# Sheet1.net
KiCad netlist of a schematic drawn in Altium Designer
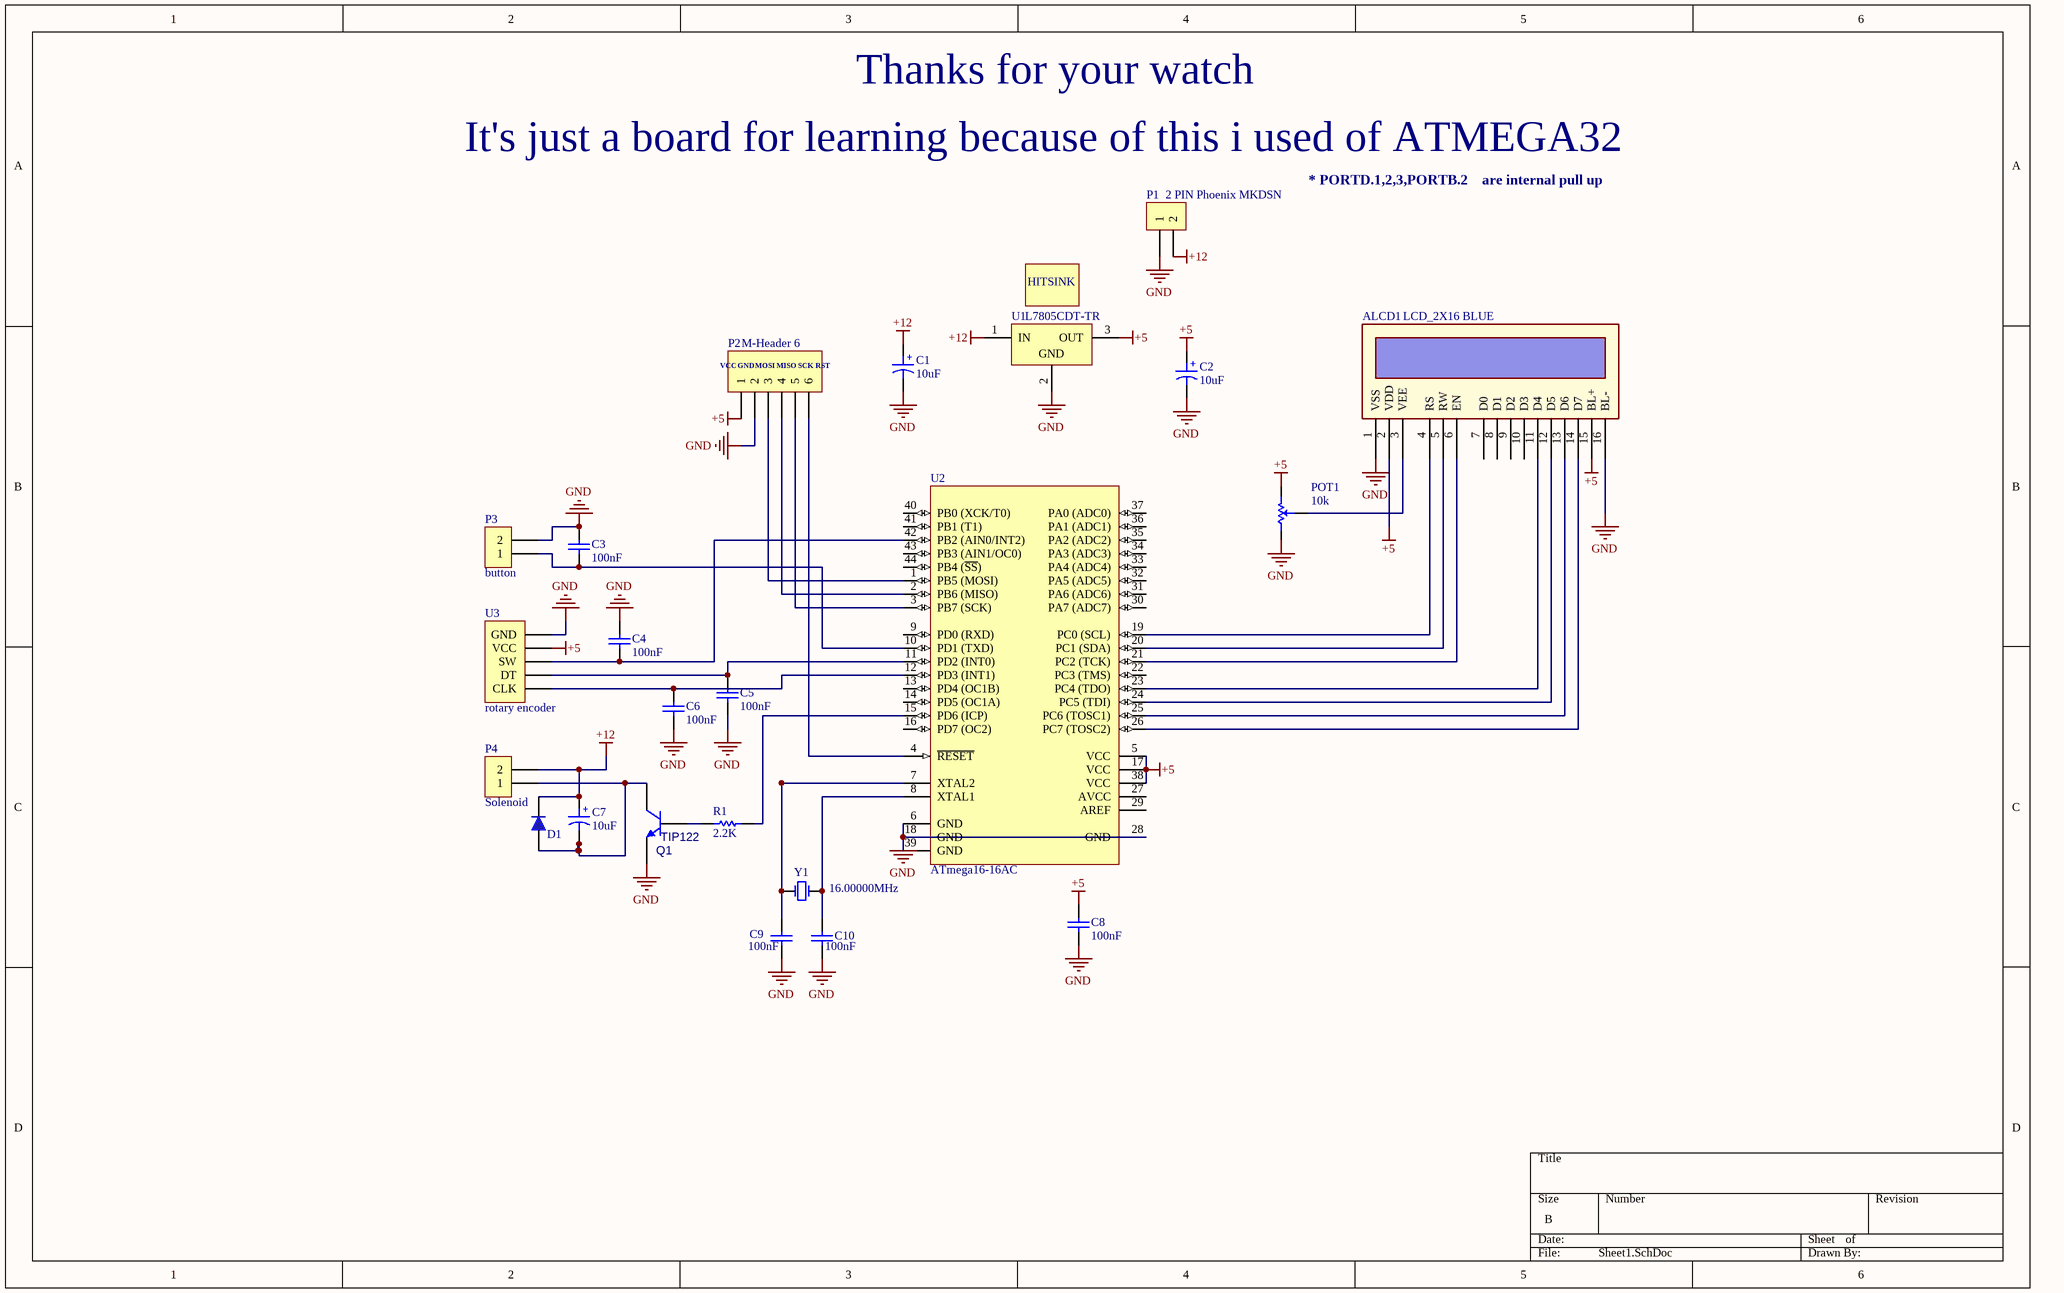
[diagram p0: Sheet1.SchDoc]

(export (version "E")
  (design (tool "Eeschema 10.0.6"))
  (components
    (comp (ref "1")
      (value "Hitsink")
      (footprint "HITSINK 1")
      (libsource (lib "Optoelectronics") (part "Hitsink"))
    )
    (comp (ref "ALCD1")
      (value "LCD_2X16 BLUE")
      (footprint "LCD_2X16 BLUE")
      (libsource (lib "Optoelectronics") (part "LCD_2X16 BLUE"))
    )
    (comp (ref "C1")
      (value "10uF")
      (footprint "Cap 6.3x12-2.5")
      (description "Capacitor DIP")
      (libsource (lib "Inactive components") (part "Capacitor DIP"))
    )
    (comp (ref "C2")
      (value "10uF")
      (footprint "Cap 6.3x12-2.5")
      (description "Capacitor DIP")
      (libsource (lib "Inactive components") (part "Capacitor DIP"))
    )
    (comp (ref "C3")
      (value "100nF")
      (footprint "CAP1206")
      (description "Capacitor SMD")
      (libsource (lib "Inactive components") (part "Capacitor SMD"))
    )
    (comp (ref "C4")
      (value "100nF")
      (footprint "CAP1206")
      (description "Capacitor SMD")
      (libsource (lib "Inactive components") (part "Capacitor SMD"))
    )
    (comp (ref "C5")
      (value "100nF")
      (footprint "CAP1206")
      (description "Capacitor SMD")
      (libsource (lib "Inactive components") (part "Capacitor SMD"))
    )
    (comp (ref "C6")
      (value "100nF")
      (footprint "CAP1206")
      (description "Capacitor SMD")
      (libsource (lib "Inactive components") (part "Capacitor SMD"))
    )
    (comp (ref "C7")
      (value "10uF")
      (footprint "Cap 5x12-2")
      (description "Capacitor DIP")
      (libsource (lib "Inactive components") (part "Capacitor DIP"))
    )
    (comp (ref "C8")
      (value "100nF")
      (footprint "CAP1206")
      (description "Capacitor SMD")
      (libsource (lib "Inactive components") (part "Capacitor SMD"))
    )
    (comp (ref "C9")
      (value "100nF")
      (footprint "CAP1206")
      (description "Capacitor SMD")
      (libsource (lib "Inactive components") (part "Capacitor SMD"))
    )
    (comp (ref "C10")
      (value "100nF")
      (footprint "CAP1206")
      (description "Capacitor SMD")
      (libsource (lib "Inactive components") (part "Capacitor SMD"))
    )
    (comp (ref "D1")
      (value "1n4007")
      (footprint "Diode 1N4007 SMD")
      (description "Diode 1n4007")
      (libsource (lib "Semiconductors") (part "Diode 1n4007"))
    )
    (comp (ref "P1")
      (value "2 PIN Phoenix MKDSN")
      (footprint "2 PIN Phoenix MKDSN")
      (libsource (lib "") (part "2 PIN Phoenix MKDSN_1"))
    )
    (comp (ref "P2")
      (value "M-Header 6")
      (footprint "M-Header 6")
      (libsource (lib "Connectors") (part "M-Header 6"))
    )
    (comp (ref "P3")
      (value "button")
      (footprint "2 PIN Phoenix MKDSN")
      (libsource (lib "Connectors") (part "2 PIN Phoenix MKDSN"))
    )
    (comp (ref "P4")
      (value "Solenoid")
      (footprint "2 PIN Phoenix MKDSN")
      (libsource (lib "Connectors") (part "2 PIN Phoenix MKDSN"))
    )
    (comp (ref "POT1")
      (value "10k")
      (footprint "POT MULTITURN")
      (libsource (lib "Inactive components") (part "Potentiometer"))
    )
    (comp (ref "Q1") (value "TIP122") (footprint "TIP122") (libsource (lib "Semiconductors") (part "TIP122")))
    (comp (ref "R1")
      (value "2.2K")
      (footprint "RES1206")
      (description "Resistor SMD")
      (libsource (lib "Inactive components") (part "Resistor SMD"))
    )
    (comp (ref "U1")
      (value "L7805CDT-TR")
      (footprint "TO-263")
      (libsource (lib "Semiconductors") (part "L7805CDT-TR"))
    )
    (comp (ref "U2")
      (value "ATmega16-16AC")
      (footprint "44A")
      (description "8-Bit AVR Microcontroller with 16K Bytes of In-System Programmable Flash Memory")
      (fields (field (name "PUBLISHER") "Altium Limited"))
      (libsource (lib "Atmel Microcontroller 8-Bit AVR") (part "ATmega16-16AC"))
    )
    (comp (ref "U3")
      (value "rotary encoder")
      (footprint "rotary encoder")
      (libsource (lib "Modules") (part "rotary encoder"))
    )
    (comp (ref "Y1")
      (value "16.00000MHz")
      (footprint "CRYSTAL Small")
      (description "XTAL DIP")
      (libsource (lib "Inactive components") (part "XTAL DIP"))
    )
  )
  (nets
    (net (code "1") (name "+5") (class "Default")
      (node (ref "ALCD1") (pin "15") (pinfunction "BL+_15") (pintype "passive"))
      (node (ref "ALCD1") (pin "2") (pinfunction "VDD_2") (pintype "passive"))
      (node (ref "C2") (pin "1") (pinfunction "1_1") (pintype "passive"))
      (node (ref "C8") (pin "2") (pinfunction "2_2") (pintype "passive"))
      (node (ref "P2") (pin "1") (pinfunction "1_1") (pintype "passive"))
      (node (ref "POT1") (pin "2") (pinfunction "CW_2") (pintype "passive"))
      (node (ref "U1") (pin "3") (pinfunction "OUT_3") (pintype "power_in"))
      (node (ref "U2") (pin "17") (pinfunction "VCC_17") (pintype "power_in"))
      (node (ref "U2") (pin "38") (pinfunction "VCC_38") (pintype "power_in"))
      (node (ref "U2") (pin "5") (pinfunction "VCC_5") (pintype "power_in"))
      (node (ref "U3") (pin "4") (pinfunction "VCC_4") (pintype "passive"))
    )
    (net (code "2") (name "+12") (class "Default")
      (node (ref "C1") (pin "1") (pinfunction "1_1") (pintype "passive"))
      (node (ref "C7") (pin "1") (pinfunction "1_1") (pintype "passive"))
      (node (ref "D1") (pin "2") (pintype "passive"))
      (node (ref "P1") (pin "2") (pinfunction "2_2") (pintype "passive"))
      (node (ref "P4") (pin "2") (pinfunction "2_2") (pintype "passive"))
      (node (ref "U1") (pin "1") (pinfunction "IN_1") (pintype "power_in"))
    )
    (net (code "3") (name "GND") (class "Default")
      (node (ref "ALCD1") (pin "1") (pinfunction "VSS_1") (pintype "passive"))
      (node (ref "ALCD1") (pin "16") (pinfunction "BL-_16") (pintype "passive"))
      (node (ref "C1") (pin "2") (pinfunction "2_2") (pintype "passive"))
      (node (ref "C10") (pin "1") (pinfunction "1_1") (pintype "passive"))
      (node (ref "C2") (pin "2") (pinfunction "2_2") (pintype "passive"))
      (node (ref "C3") (pin "2") (pinfunction "2_2") (pintype "passive"))
      (node (ref "C4") (pin "2") (pinfunction "2_2") (pintype "passive"))
      (node (ref "C5") (pin "1") (pinfunction "1_1") (pintype "passive"))
      (node (ref "C6") (pin "1") (pinfunction "1_1") (pintype "passive"))
      (node (ref "C8") (pin "1") (pinfunction "1_1") (pintype "passive"))
      (node (ref "C9") (pin "1") (pinfunction "1_1") (pintype "passive"))
      (node (ref "P1") (pin "1") (pinfunction "1_1") (pintype "passive"))
      (node (ref "P2") (pin "2") (pinfunction "2_2") (pintype "passive"))
      (node (ref "P3") (pin "2") (pinfunction "2_2") (pintype "passive"))
      (node (ref "POT1") (pin "1") (pinfunction "CCW_1") (pintype "passive"))
      (node (ref "Q1") (pin "3") (pinfunction "E_3") (pintype "passive"))
      (node (ref "U1") (pin "2") (pinfunction "GND_2") (pintype "power_in"))
      (node (ref "U2") (pin "18") (pinfunction "GND_18") (pintype "power_in"))
      (node (ref "U2") (pin "28") (pinfunction "GND_28") (pintype "power_in"))
      (node (ref "U2") (pin "39") (pinfunction "GND_39") (pintype "power_in"))
      (node (ref "U2") (pin "6") (pinfunction "GND_6") (pintype "power_in"))
      (node (ref "U3") (pin "5") (pinfunction "GND_5") (pintype "passive"))
    )
    (net (code "4") (name "Net-(ALCD1-D4)") (class "Default")
      (node (ref "ALCD1") (pin "11") (pinfunction "D4_11") (pintype "passive"))
      (node (ref "U2") (pin "23") (pinfunction "PC4_(TDO)_23") (pintype "bidirectional"))
    )
    (net (code "5") (name "Net-(ALCD1-D5)") (class "Default")
      (node (ref "ALCD1") (pin "12") (pinfunction "D5_12") (pintype "passive"))
      (node (ref "U2") (pin "24") (pinfunction "PC5_(TDI)_24") (pintype "bidirectional"))
    )
    (net (code "6") (name "Net-(ALCD1-D6)") (class "Default")
      (node (ref "ALCD1") (pin "13") (pinfunction "D6_13") (pintype "passive"))
      (node (ref "U2") (pin "25") (pinfunction "PC6_(TOSC1)_25") (pintype "bidirectional"))
    )
    (net (code "7") (name "Net-(ALCD1-D7)") (class "Default")
      (node (ref "ALCD1") (pin "14") (pinfunction "D7_14") (pintype "passive"))
      (node (ref "U2") (pin "26") (pinfunction "PC7_(TOSC2)_26") (pintype "bidirectional"))
    )
    (net (code "8") (name "Net-(ALCD1-EN)") (class "Default")
      (node (ref "ALCD1") (pin "6") (pinfunction "EN_6") (pintype "passive"))
      (node (ref "U2") (pin "21") (pinfunction "PC2_(TCK)_21") (pintype "bidirectional"))
    )
    (net (code "9") (name "Net-(ALCD1-RS)") (class "Default")
      (node (ref "ALCD1") (pin "4") (pinfunction "RS_4") (pintype "passive"))
      (node (ref "U2") (pin "19") (pinfunction "PC0_(SCL)_19") (pintype "bidirectional"))
    )
    (net (code "10") (name "Net-(ALCD1-RW)") (class "Default")
      (node (ref "ALCD1") (pin "5") (pinfunction "RW_5") (pintype "passive"))
      (node (ref "U2") (pin "20") (pinfunction "PC1_(SDA)_20") (pintype "bidirectional"))
    )
    (net (code "11") (name "Net-(ALCD1-VEE)") (class "Default")
      (node (ref "ALCD1") (pin "3") (pinfunction "VEE_3") (pintype "passive"))
      (node (ref "POT1") (pin "3") (pinfunction "SetPoint_3") (pintype "passive"))
    )
    (net (code "12") (name "Net-(Q1-B)") (class "Default")
      (node (ref "Q1") (pin "1") (pinfunction "B_1") (pintype "passive"))
      (node (ref "R1") (pin "1") (pinfunction "1_1") (pintype "passive"))
    )
    (net (code "13") (name "Net-(Q1-C)") (class "Default")
      (node (ref "C7") (pin "2") (pinfunction "2_2") (pintype "passive"))
      (node (ref "D1") (pin "1") (pintype "passive"))
      (node (ref "P4") (pin "1") (pinfunction "1_1") (pintype "passive"))
      (node (ref "Q1") (pin "2") (pinfunction "C_2") (pintype "passive"))
    )
    (net (code "14") (name "Net-(U2-PB2_(AIN0{slash}INT2))") (class "Default")
      (node (ref "C4") (pin "1") (pinfunction "1_1") (pintype "passive"))
      (node (ref "U2") (pin "42") (pinfunction "PB2_(AIN0/INT2)_42") (pintype "bidirectional"))
      (node (ref "U3") (pin "3") (pinfunction "SW_3") (pintype "passive"))
    )
    (net (code "15") (name "Net-(U2-PB5_(MOSI))") (class "Default")
      (node (ref "P2") (pin "3") (pinfunction "3_3") (pintype "passive"))
      (node (ref "U2") (pin "1") (pinfunction "PB5_(MOSI)_1") (pintype "bidirectional"))
    )
    (net (code "16") (name "Net-(U2-PB6_(MISO))") (class "Default")
      (node (ref "P2") (pin "4") (pinfunction "4_4") (pintype "passive"))
      (node (ref "U2") (pin "2") (pinfunction "PB6_(MISO)_2") (pintype "bidirectional"))
    )
    (net (code "17") (name "Net-(U2-PB7_(SCK))") (class "Default")
      (node (ref "P2") (pin "5") (pinfunction "5_5") (pintype "passive"))
      (node (ref "U2") (pin "3") (pinfunction "PB7_(SCK)_3") (pintype "bidirectional"))
    )
    (net (code "18") (name "Net-(U2-PD1_(TXD))") (class "Default")
      (node (ref "C3") (pin "1") (pinfunction "1_1") (pintype "passive"))
      (node (ref "P3") (pin "1") (pinfunction "1_1") (pintype "passive"))
      (node (ref "U2") (pin "10") (pinfunction "PD1_(TXD)_10") (pintype "bidirectional"))
    )
    (net (code "19") (name "Net-(U2-PD2_(INT0))") (class "Default")
      (node (ref "C5") (pin "2") (pinfunction "2_2") (pintype "passive"))
      (node (ref "U2") (pin "11") (pinfunction "PD2_(INT0)_11") (pintype "bidirectional"))
      (node (ref "U3") (pin "2") (pinfunction "DT_2") (pintype "passive"))
    )
    (net (code "20") (name "Net-(U2-PD3_(INT1))") (class "Default")
      (node (ref "C6") (pin "2") (pinfunction "2_2") (pintype "passive"))
      (node (ref "U2") (pin "12") (pinfunction "PD3_(INT1)_12") (pintype "bidirectional"))
      (node (ref "U3") (pin "1") (pinfunction "CLK_1") (pintype "passive"))
    )
    (net (code "21") (name "Net-(U2-PD6_(ICP))") (class "Default")
      (node (ref "R1") (pin "2") (pinfunction "2_2") (pintype "passive"))
      (node (ref "U2") (pin "15") (pinfunction "PD6_(ICP)_15") (pintype "bidirectional"))
    )
    (net (code "22") (name "Net-(U2-XTAL1)") (class "Default")
      (node (ref "C10") (pin "2") (pinfunction "2_2") (pintype "passive"))
      (node (ref "U2") (pin "8") (pinfunction "XTAL1_8") (pintype "passive"))
      (node (ref "Y1") (pin "1") (pinfunction "OSC1_1") (pintype "passive"))
    )
    (net (code "23") (name "Net-(U2-XTAL2)") (class "Default")
      (node (ref "C9") (pin "2") (pinfunction "2_2") (pintype "passive"))
      (node (ref "U2") (pin "7") (pinfunction "XTAL2_7") (pintype "passive"))
      (node (ref "Y1") (pin "2") (pinfunction "OSC2_2") (pintype "passive"))
    )
    (net (code "24") (name "Net-(U2-~{RESET})") (class "Default")
      (node (ref "P2") (pin "6") (pinfunction "6_6") (pintype "passive"))
      (node (ref "U2") (pin "4") (pinfunction "~{RESET}_4") (pintype "input"))
    )
    (net (code "25") (name "unconnected-(ALCD1-D0-Pad7)") (class "Default")
      (node (ref "ALCD1") (pin "7") (pinfunction "D0_7") (pintype "passive"))
    )
    (net (code "26") (name "unconnected-(ALCD1-D1-Pad8)") (class "Default")
      (node (ref "ALCD1") (pin "8") (pinfunction "D1_8") (pintype "passive"))
    )
    (net (code "27") (name "unconnected-(ALCD1-D2-Pad9)") (class "Default")
      (node (ref "ALCD1") (pin "9") (pinfunction "D2_9") (pintype "passive"))
    )
    (net (code "28") (name "unconnected-(ALCD1-D3-Pad10)") (class "Default")
      (node (ref "ALCD1") (pin "10") (pinfunction "D3_10") (pintype "passive"))
    )
    (net (code "29") (name "unconnected-(U2-AREF-Pad29)") (class "Default")
      (node (ref "U2") (pin "29") (pinfunction "AREF_29") (pintype "passive"))
    )
    (net (code "30") (name "unconnected-(U2-AVCC-Pad27)") (class "Default")
      (node (ref "U2") (pin "27") (pinfunction "AVCC_27") (pintype "power_in"))
    )
    (net (code "31") (name "unconnected-(U2-PA0_(ADC0)-Pad37)") (class "Default")
      (node (ref "U2") (pin "37") (pinfunction "PA0_(ADC0)_37") (pintype "bidirectional"))
    )
    (net (code "32") (name "unconnected-(U2-PA1_(ADC1)-Pad36)") (class "Default")
      (node (ref "U2") (pin "36") (pinfunction "PA1_(ADC1)_36") (pintype "bidirectional"))
    )
    (net (code "33") (name "unconnected-(U2-PA2_(ADC2)-Pad35)") (class "Default")
      (node (ref "U2") (pin "35") (pinfunction "PA2_(ADC2)_35") (pintype "bidirectional"))
    )
    (net (code "34") (name "unconnected-(U2-PA3_(ADC3)-Pad34)") (class "Default")
      (node (ref "U2") (pin "34") (pinfunction "PA3_(ADC3)_34") (pintype "bidirectional"))
    )
    (net (code "35") (name "unconnected-(U2-PA4_(ADC4)-Pad33)") (class "Default")
      (node (ref "U2") (pin "33") (pinfunction "PA4_(ADC4)_33") (pintype "bidirectional"))
    )
    (net (code "36") (name "unconnected-(U2-PA5_(ADC5)-Pad32)") (class "Default")
      (node (ref "U2") (pin "32") (pinfunction "PA5_(ADC5)_32") (pintype "bidirectional"))
    )
    (net (code "37") (name "unconnected-(U2-PA6_(ADC6)-Pad31)") (class "Default")
      (node (ref "U2") (pin "31") (pinfunction "PA6_(ADC6)_31") (pintype "bidirectional"))
    )
    (net (code "38") (name "unconnected-(U2-PA7_(ADC7)-Pad30)") (class "Default")
      (node (ref "U2") (pin "30") (pinfunction "PA7_(ADC7)_30") (pintype "bidirectional"))
    )
    (net (code "39") (name "unconnected-(U2-PB0_(XCK{slash}T0)-Pad40)") (class "Default")
      (node (ref "U2") (pin "40") (pinfunction "PB0_(XCK/T0)_40") (pintype "bidirectional"))
    )
    (net (code "40") (name "unconnected-(U2-PB1_(T1)-Pad41)") (class "Default")
      (node (ref "U2") (pin "41") (pinfunction "PB1_(T1)_41") (pintype "bidirectional"))
    )
    (net (code "41") (name "unconnected-(U2-PB3_(AIN1{slash}OC0)-Pad43)") (class "Default")
      (node (ref "U2") (pin "43") (pinfunction "PB3_(AIN1/OC0)_43") (pintype "bidirectional"))
    )
    (net (code "42") (name "unconnected-(U2-PB4_(~{SS})-Pad44)") (class "Default")
      (node (ref "U2") (pin "44") (pinfunction "PB4_(~{SS})_44") (pintype "bidirectional"))
    )
    (net (code "43") (name "unconnected-(U2-PC3_(TMS)-Pad22)") (class "Default")
      (node (ref "U2") (pin "22") (pinfunction "PC3_(TMS)_22") (pintype "bidirectional"))
    )
    (net (code "44") (name "unconnected-(U2-PD0_(RXD)-Pad9)") (class "Default")
      (node (ref "U2") (pin "9") (pinfunction "PD0_(RXD)_9") (pintype "bidirectional"))
    )
    (net (code "45") (name "unconnected-(U2-PD4_(OC1B)-Pad13)") (class "Default")
      (node (ref "U2") (pin "13") (pinfunction "PD4_(OC1B)_13") (pintype "bidirectional"))
    )
    (net (code "46") (name "unconnected-(U2-PD5_(OC1A)-Pad14)") (class "Default")
      (node (ref "U2") (pin "14") (pinfunction "PD5_(OC1A)_14") (pintype "bidirectional"))
    )
    (net (code "47") (name "unconnected-(U2-PD7_(OC2)-Pad16)") (class "Default")
      (node (ref "U2") (pin "16") (pinfunction "PD7_(OC2)_16") (pintype "bidirectional"))
    )
  )
)
